# microSD-adapter.net
KiCad netlist of a schematic drawn in EAGLE
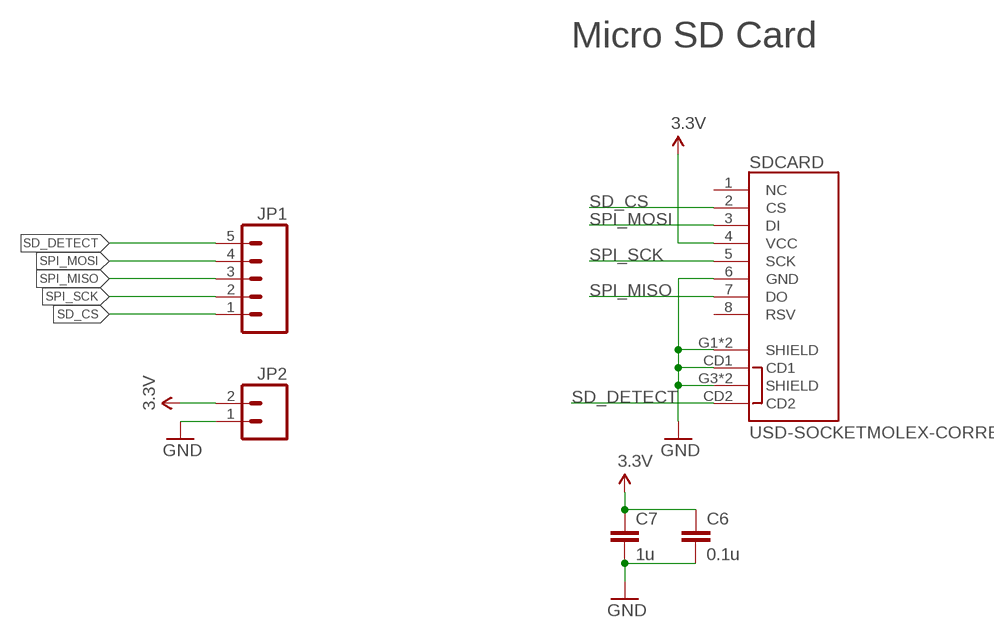
[diagram p0: schematic, sheet 1]

(export (version "E")
  (design (tool "Eeschema 10.0.6"))
  (components
    (comp (ref "C6")
      (value "0.1u")
      (footprint "eagle-import:C0805")
      (fields (field (name "PARTNO") "08055C104KAT2A"))
      (libsource (lib "eagle-import") (part "C-EUC0805"))
    )
    (comp (ref "C7")
      (value "1u")
      (footprint "eagle-import:C0805")
      (fields (field (name "PARTNO") "CC0805KKX7R7BB105"))
      (libsource (lib "eagle-import") (part "C-EUC0805"))
    )
    (comp (ref "JP1")
      (value "M05PTH")
      (footprint "eagle-import:1X05")
      (libsource (lib "eagle-import") (part "M05PTH"))
    )
    (comp (ref "JP2")
      (value "M02PTH")
      (footprint "eagle-import:1X02")
      (libsource (lib "eagle-import") (part "M02PTH"))
    )
    (comp (ref "SDCARD")
      (value "USD-SOCKETMOLEX-CORRECT")
      (footprint "eagle-import:MICRO-SD-MOLEX-CORRECT")
      (fields (field (name "PARTNO") "1040310811"))
      (libsource (lib "eagle-import") (part "USD-SOCKETMOLEX-CORRECT"))
    )
  )
  (nets
    (net (code "1") (name "3.3V") (class "Default")
      (node (ref "C6") (pin "1") (pinfunction "1_1") (pintype "passive"))
      (node (ref "C7") (pin "1") (pinfunction "1_1") (pintype "passive"))
      (node (ref "JP2") (pin "2") (pinfunction "2_2") (pintype "passive"))
      (node (ref "SDCARD") (pin "4") (pinfunction "VCC_4") (pintype "bidirectional"))
    )
    (net (code "2") (name "GND") (class "Default")
      (node (ref "C6") (pin "2") (pinfunction "2_2") (pintype "passive"))
      (node (ref "C7") (pin "2") (pinfunction "2_2") (pintype "passive"))
      (node (ref "JP2") (pin "1") (pinfunction "1_1") (pintype "passive"))
      (node (ref "SDCARD") (pin "6") (pinfunction "GND_6") (pintype "bidirectional"))
      (node (ref "SDCARD") (pin "CD1") (pinfunction "CD1_CD1") (pintype "bidirectional"))
      (node (ref "SDCARD") (pin "G1") (pinfunction "SHIELD_G1") (pintype "bidirectional"))
      (node (ref "SDCARD") (pin "G2") (pinfunction "SHIELD_G2") (pintype "bidirectional"))
      (node (ref "SDCARD") (pin "G3") (pinfunction "SHIELD_G3") (pintype "bidirectional"))
      (node (ref "SDCARD") (pin "G4") (pinfunction "SHIELD_G4") (pintype "bidirectional"))
    )
    (net (code "3") (name "SD_CS") (class "Default")
      (node (ref "JP1") (pin "1") (pinfunction "1_1") (pintype "passive"))
      (node (ref "SDCARD") (pin "2") (pinfunction "CS_2") (pintype "bidirectional"))
    )
    (net (code "4") (name "SD_DETECT") (class "Default")
      (node (ref "JP1") (pin "5") (pinfunction "5_5") (pintype "passive"))
      (node (ref "SDCARD") (pin "CD2") (pinfunction "CD2_CD2") (pintype "bidirectional"))
    )
    (net (code "5") (name "SPI_MISO") (class "Default")
      (node (ref "JP1") (pin "3") (pinfunction "3_3") (pintype "passive"))
      (node (ref "SDCARD") (pin "7") (pinfunction "DO_7") (pintype "bidirectional"))
    )
    (net (code "6") (name "SPI_MOSI") (class "Default")
      (node (ref "JP1") (pin "4") (pinfunction "4_4") (pintype "passive"))
      (node (ref "SDCARD") (pin "3") (pinfunction "DI_3") (pintype "bidirectional"))
    )
    (net (code "7") (name "SPI_SCK") (class "Default")
      (node (ref "JP1") (pin "2") (pinfunction "2_2") (pintype "passive"))
      (node (ref "SDCARD") (pin "5") (pinfunction "SCK_5") (pintype "bidirectional"))
    )
    (net (code "8") (name "unconnected-(SDCARD-NC-Pad1)") (class "Default")
      (node (ref "SDCARD") (pin "1") (pinfunction "NC_1") (pintype "bidirectional"))
    )
    (net (code "9") (name "unconnected-(SDCARD-RSV-Pad8)") (class "Default")
      (node (ref "SDCARD") (pin "8") (pinfunction "RSV_8") (pintype "bidirectional"))
    )
  )
)
